# MCU.net
KiCad netlist of a schematic drawn in Altium Designer
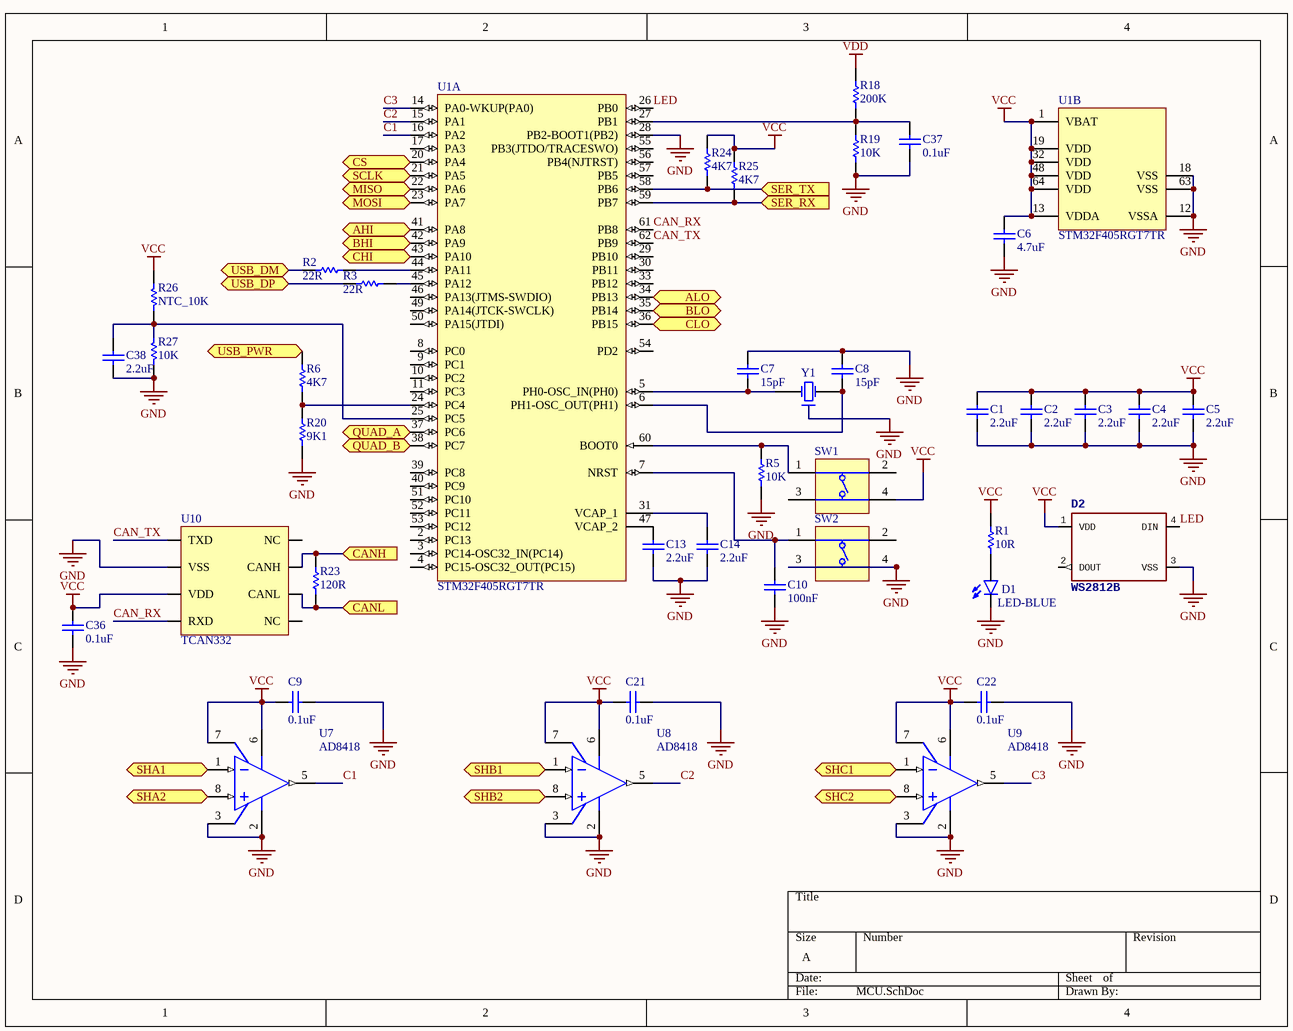
[diagram p0: MCU.SchDoc]

(export (version "E")
  (design (tool "Eeschema 10.0.6"))
  (components
    (comp (ref "C1")
      (value "2.2uF")
      (footprint "CAPC0402(1005)60_M")
      (description "CAP 2.2uF 6.3V ±10% 0402 (1005 Metric) Thickness 0.6mm SMD")
      (fields (field (name "TOLERANCE") "Â±10%"))
      (libsource (lib "Altium Content Vault") (part "CMP-1034-02125-1"))
    )
    (comp (ref "C2")
      (value "2.2uF")
      (footprint "CAPC0402(1005)60_M")
      (description "CAP 2.2uF 6.3V ±10% 0402 (1005 Metric) Thickness 0.6mm SMD")
      (fields (field (name "TOLERANCE") "Â±10%"))
      (libsource (lib "Altium Content Vault") (part "CMP-1034-02125-1"))
    )
    (comp (ref "C3")
      (value "2.2uF")
      (footprint "CAPC0402(1005)60_M")
      (description "CAP 2.2uF 6.3V ±10% 0402 (1005 Metric) Thickness 0.6mm SMD")
      (fields (field (name "TOLERANCE") "Â±10%"))
      (libsource (lib "Altium Content Vault") (part "CMP-1034-02125-1"))
    )
    (comp (ref "C4")
      (value "2.2uF")
      (footprint "CAPC0402(1005)60_M")
      (description "CAP 2.2uF 6.3V ±10% 0402 (1005 Metric) Thickness 0.6mm SMD")
      (fields (field (name "TOLERANCE") "Â±10%"))
      (libsource (lib "Altium Content Vault") (part "CMP-1034-02125-1"))
    )
    (comp (ref "C5")
      (value "2.2uF")
      (footprint "CAPC0402(1005)60_M")
      (description "CAP 2.2uF 6.3V ±10% 0402 (1005 Metric) Thickness 0.6mm SMD")
      (fields (field (name "TOLERANCE") "Â±10%"))
      (libsource (lib "Altium Content Vault") (part "CMP-1034-02125-1"))
    )
    (comp (ref "C6")
      (value "4.7uF")
      (footprint "CAPC0402(1005)60_L")
      (description "CAP 4.7uF 6.3V ±10% 0402 (1005 Metric) Thickness 0.6mm SMD")
      (fields (field (name "TOLERANCE") "Â±10%"))
      (libsource (lib "Altium Content Vault") (part "CMP-1034-02136-1"))
    )
    (comp (ref "C7")
      (value "15pF")
      (footprint "CAPC0402(1005)60_M")
      (description "CAP 15nF 6.3V ±10% 0402 (1005 Metric) Thickness 0.6mm SMD")
      (fields (field (name "TOLERANCE") "Â±10%"))
      (libsource (lib "Altium Content Vault") (part "CMP-1034-01906-1"))
    )
    (comp (ref "C8")
      (value "15pF")
      (footprint "CAPC0402(1005)60_M")
      (description "CAP 15nF 6.3V ±10% 0402 (1005 Metric) Thickness 0.6mm SMD")
      (fields (field (name "TOLERANCE") "Â±10%"))
      (libsource (lib "Altium Content Vault") (part "CMP-1034-01906-1"))
    )
    (comp (ref "C9")
      (value "0.1uF")
      (footprint "CAPC0402(1005)60_M")
      (description "CAP 100nF 6.3V ±5% 0402 (1005 Metric) Thickness 0.6mm SMD")
      (fields (field (name "TOLERANCE") "Â±5%"))
      (libsource (lib "Altium Content Vault") (part "CAP"))
    )
    (comp (ref "C10")
      (value "100nF")
      (footprint "CAPC0402(1005)60_M")
      (description "CAP 100nF 6.3V ±5% 0402 (1005 Metric) Thickness 0.6mm SMD")
      (fields (field (name "TOLERANCE") "Â±5%"))
      (libsource (lib "Altium Content Vault") (part "CAP"))
    )
    (comp (ref "C13")
      (value "2.2uF")
      (footprint "CAPC0402(1005)60_M")
      (description "CAP 2.2uF 6.3V ±10% 0402 (1005 Metric) Thickness 0.6mm SMD")
      (fields (field (name "TOLERANCE") "Â±10%"))
      (libsource (lib "Altium Content Vault") (part "CMP-1034-02125-1"))
    )
    (comp (ref "C14")
      (value "2.2uF")
      (footprint "CAPC0402(1005)60_M")
      (description "CAP 2.2uF 6.3V ±10% 0402 (1005 Metric) Thickness 0.6mm SMD")
      (fields (field (name "TOLERANCE") "Â±10%"))
      (libsource (lib "Altium Content Vault") (part "CMP-1034-02125-1"))
    )
    (comp (ref "C21")
      (value "0.1uF")
      (footprint "CAPC0402(1005)60_M")
      (description "CAP 100nF 6.3V ±5% 0402 (1005 Metric) Thickness 0.6mm SMD")
      (fields (field (name "TOLERANCE") "Â±5%"))
      (libsource (lib "Altium Content Vault") (part "CAP"))
    )
    (comp (ref "C22")
      (value "0.1uF")
      (footprint "CAPC0402(1005)60_M")
      (description "CAP 100nF 6.3V ±5% 0402 (1005 Metric) Thickness 0.6mm SMD")
      (fields (field (name "TOLERANCE") "Â±5%"))
      (libsource (lib "Altium Content Vault") (part "CAP"))
    )
    (comp (ref "C36")
      (value "0.1uF")
      (footprint "CAPC0402(1005)60_M")
      (description "CAP 100nF 6.3V ±5% 0402 (1005 Metric) Thickness 0.6mm SMD")
      (fields (field (name "TOLERANCE") "Â±5%"))
      (libsource (lib "Altium Content Vault") (part "CMP-1034-02060-1"))
    )
    (comp (ref "C37")
      (value "0.1uF")
      (footprint "CAPC0402(1005)60_L")
      (description "CAP 100nF 6.3V ±5% 0402 (1005 Metric) Thickness 0.6mm SMD")
      (fields (field (name "TOLERANCE") "Â±5%"))
      (libsource (lib "Altium Content Vault") (part "CMP-1034-02060-1"))
    )
    (comp (ref "C38")
      (value "2.2uF")
      (footprint "CAPC0402(1005)60_L")
      (description "CAP 2.2uF 6.3V ±10% 0402 (1005 Metric) Thickness 0.6mm SMD")
      (fields (field (name "TOLERANCE") "Â±10%"))
      (libsource (lib "Altium Content Vault") (part "CAP"))
    )
    (comp (ref "D1")
      (value "LED-BLUE")
      (footprint "LED-1206")
      (libsource (lib "Components") (part "LED-BLUE1206"))
    )
    (comp (ref "D2") (value "WS2812B") (footprint "WS2812B") (libsource (lib "Components") (part "WS2812B")))
    (comp (ref "R1")
      (value "10R")
      (footprint "RESC0402(1005)_N")
      (description "10R 0.063W 5% 0402 (1005 Metric)  SMD")
      (fields (field (name "POWER") "0.063 W") (field (name "TOLERANCE") "5 %"))
      (libsource (lib "Altium Content Vault") (part "CMP-1011-00026-1"))
    )
    (comp (ref "R2")
      (value "22R")
      (footprint "RESC0402(1005)_N")
      (description "22R 0.063W 5% 0402 (1005 Metric)  SMD")
      (fields (field (name "POWER") "0.063 W") (field (name "TOLERANCE") "5 %"))
      (libsource (lib "Altium Content Vault") (part "CMP-1011-00034-1"))
    )
    (comp (ref "R3")
      (value "22R")
      (footprint "RESC0402(1005)_N")
      (description "22R 0.063W 5% 0402 (1005 Metric)  SMD")
      (fields (field (name "POWER") "0.063 W") (field (name "TOLERANCE") "5 %"))
      (libsource (lib "Altium Content Vault") (part "CMP-1011-00034-1"))
    )
    (comp (ref "R5")
      (value "10K")
      (footprint "RESC0402(1005)_N")
      (description "10K 0.063W 5% 0402 (1005 Metric)  SMD")
      (fields (field (name "TOLERANCE") "5 %") (field (name "POWER") "0.063 W"))
      (libsource (lib "Altium Content Vault") (part "RES"))
    )
    (comp (ref "R6")
      (value "4K7")
      (footprint "RESC0402(1005)_L")
      (description "4K7 0.063W 5% 0402 (1005 Metric)  SMD")
      (fields (field (name "TOLERANCE") "5 %") (field (name "POWER") "0.063 W"))
      (libsource (lib "Altium Content Vault") (part "RES"))
    )
    (comp (ref "R18")
      (value "200K")
      (footprint "RESC0402(1005)_N")
      (description "5K1 0.063W 5% 0402 (1005 Metric)  SMD")
      (fields (field (name "TOLERANCE") "5 %") (field (name "POWER") "0.063 W"))
      (libsource (lib "Altium Content Vault") (part "CMP-1011-00091-1"))
    )
    (comp (ref "R19")
      (value "10K")
      (footprint "RESC0402(1005)_N")
      (description "10K 0.063W 5% 0402 (1005 Metric)  SMD")
      (fields (field (name "TOLERANCE") "5 %") (field (name "POWER") "0.063 W"))
      (libsource (lib "Altium Content Vault") (part "RES"))
    )
    (comp (ref "R20")
      (value "9K1")
      (footprint "RESC0402(1005)_M")
      (description "9K1 0.063W 5% 0402 (1005 Metric)  SMD")
      (fields (field (name "TOLERANCE") "5 %") (field (name "POWER") "0.063 W"))
      (libsource (lib "Altium Content Vault") (part "RES"))
    )
    (comp (ref "R23")
      (value "120R")
      (footprint "RESC0402(1005)_N")
      (description "120R 0.063W 5% 0402 (1005 Metric)  SMD")
      (fields (field (name "TOLERANCE") "5 %") (field (name "POWER") "0.063 W"))
      (libsource (lib "Altium Content Vault") (part "RES"))
    )
    (comp (ref "R24")
      (value "4K7")
      (footprint "RESC0402(1005)_L")
      (description "4K7 0.063W 5% 0402 (1005 Metric)  SMD")
      (fields (field (name "TOLERANCE") "5 %") (field (name "POWER") "0.063 W"))
      (libsource (lib "Altium Content Vault") (part "RES"))
    )
    (comp (ref "R25")
      (value "4K7")
      (footprint "RESC0402(1005)_L")
      (description "4K7 0.063W 5% 0402 (1005 Metric)  SMD")
      (fields (field (name "TOLERANCE") "5 %") (field (name "POWER") "0.063 W"))
      (libsource (lib "Altium Content Vault") (part "RES"))
    )
    (comp (ref "R26")
      (value "NTC_10K")
      (footprint "RESC0402(1005)_L")
      (description "10K 0.063W 1% 0402 (1005 Metric)  SMD")
      (fields (field (name "TOLERANCE") "1 %") (field (name "POWER") "0.063 W"))
      (libsource (lib "Altium Content Vault") (part "CMP-1011-00623-1"))
    )
    (comp (ref "R27")
      (value "10K")
      (footprint "RESC0402(1005)_L")
      (description "10K 0.063W 1% 0402 (1005 Metric)  SMD")
      (fields (field (name "TOLERANCE") "1 %") (field (name "POWER") "0.063 W"))
      (libsource (lib "Altium Content Vault") (part "CMP-1011-00623-1"))
    )
    (comp (ref "SW1")
      (value "~")
      (footprint "SWITCH")
      (description "Switch, SPNO Push Button SMD")
      (fields (field (name "MANUFACTURER") "Diptronics") (field (name "PARTNUMBER") "DTSM-61NT/R"))
      (libsource (lib "altium-import") (part "root_0_DIPT-DTSM-6_"))
    )
    (comp (ref "SW2")
      (value "~")
      (footprint "SWITCH")
      (description "Switch, SPNO Push Button SMD")
      (fields (field (name "MANUFACTURER") "Diptronics") (field (name "PARTNUMBER") "DTSM-61NT/R"))
      (libsource (lib "altium-import") (part "root_0_DIPT-DTSM-6_"))
    )
    (comp (ref "U1")
      (value "STM32F405RGT7TR")
      (footprint "STM-LQFP64_V")
      (fields (field (name "MANUFACTURER") "STMicroelectronics"))
      (libsource (lib "Altium Content Vault") (part "MC-ARM-STM32F4X5-SQ64"))
    )
    (comp (ref "U7") (value "AD8418") (footprint "MSOP-8") (libsource (lib "Components") (part "AD8418")))
    (comp (ref "U8") (value "AD8418") (footprint "MSOP-8") (libsource (lib "Components") (part "AD8418")))
    (comp (ref "U9") (value "AD8418") (footprint "MSOP-8") (libsource (lib "Components") (part "AD8418")))
    (comp (ref "U10") (value "TCAN332") (footprint "SOIC8") (libsource (lib "Components") (part "TCAN332")))
    (comp (ref "Y1")
      (value "~")
      (footprint "ABRA-ABM3B-4_V")
      (libsource (lib "Components") (part "ABRA-ABM3B-4"))
    )
  )
  (nets
    (net (code "1") (name "/AHI") (class "Default")
      (node (ref "U1") (pin "41") (pinfunction "PA8_41") (pintype "bidirectional"))
    )
    (net (code "2") (name "/ALO") (class "Default")
      (node (ref "U1") (pin "34") (pinfunction "PB13_34") (pintype "bidirectional"))
    )
    (net (code "3") (name "/BHI") (class "Default")
      (node (ref "U1") (pin "42") (pinfunction "PA9_42") (pintype "bidirectional"))
    )
    (net (code "4") (name "/BLO") (class "Default")
      (node (ref "U1") (pin "35") (pinfunction "PB14_35") (pintype "bidirectional"))
    )
    (net (code "5") (name "/C1") (class "Default")
      (node (ref "U1") (pin "16") (pinfunction "PA2_16") (pintype "bidirectional"))
      (node (ref "U7") (pin "5") (pinfunction "OUT_5") (pintype "output"))
    )
    (net (code "6") (name "/C2") (class "Default")
      (node (ref "U1") (pin "15") (pinfunction "PA1_15") (pintype "bidirectional"))
      (node (ref "U8") (pin "5") (pinfunction "OUT_5") (pintype "output"))
    )
    (net (code "7") (name "/C3") (class "Default")
      (node (ref "U1") (pin "14") (pinfunction "PA0-WKUP(PA0)_14") (pintype "bidirectional"))
      (node (ref "U9") (pin "5") (pinfunction "OUT_5") (pintype "output"))
    )
    (net (code "8") (name "/CANH") (class "Default")
      (node (ref "R23") (pin "2") (pinfunction "2_2") (pintype "passive"))
      (node (ref "U10") (pin "7") (pinfunction "CANH_7") (pintype "passive"))
    )
    (net (code "9") (name "/CANL") (class "Default")
      (node (ref "R23") (pin "1") (pinfunction "1_1") (pintype "passive"))
      (node (ref "U10") (pin "6") (pinfunction "CANL_6") (pintype "passive"))
    )
    (net (code "10") (name "/CAN_RX") (class "Default")
      (node (ref "U1") (pin "61") (pinfunction "PB8_61") (pintype "bidirectional"))
      (node (ref "U10") (pin "4") (pinfunction "RXD_4") (pintype "passive"))
    )
    (net (code "11") (name "/CAN_TX") (class "Default")
      (node (ref "U1") (pin "62") (pinfunction "PB9_62") (pintype "bidirectional"))
      (node (ref "U10") (pin "1") (pinfunction "TXD_1") (pintype "passive"))
    )
    (net (code "12") (name "/CHI") (class "Default")
      (node (ref "U1") (pin "43") (pinfunction "PA10_43") (pintype "bidirectional"))
    )
    (net (code "13") (name "/CLO") (class "Default")
      (node (ref "U1") (pin "36") (pinfunction "PB15_36") (pintype "bidirectional"))
    )
    (net (code "14") (name "/CS") (class "Default")
      (node (ref "U1") (pin "20") (pinfunction "PA4_20") (pintype "bidirectional"))
    )
    (net (code "15") (name "/LED") (class "Default")
      (node (ref "D2") (pin "4") (pinfunction "DIN_4") (pintype "passive"))
      (node (ref "U1") (pin "26") (pinfunction "PB0_26") (pintype "bidirectional"))
    )
    (net (code "16") (name "/MISO") (class "Default")
      (node (ref "U1") (pin "22") (pinfunction "PA6_22") (pintype "bidirectional"))
    )
    (net (code "17") (name "/MOSI") (class "Default")
      (node (ref "U1") (pin "23") (pinfunction "PA7_23") (pintype "bidirectional"))
    )
    (net (code "18") (name "/QUAD_A") (class "Default")
      (node (ref "U1") (pin "37") (pinfunction "PC6_37") (pintype "bidirectional"))
    )
    (net (code "19") (name "/QUAD_B") (class "Default")
      (node (ref "U1") (pin "38") (pinfunction "PC7_38") (pintype "bidirectional"))
    )
    (net (code "20") (name "/SCLK") (class "Default")
      (node (ref "U1") (pin "21") (pinfunction "PA5_21") (pintype "bidirectional"))
    )
    (net (code "21") (name "/SER_RX") (class "Default")
      (node (ref "R25") (pin "1") (pinfunction "1_1") (pintype "passive"))
      (node (ref "U1") (pin "59") (pinfunction "PB7_59") (pintype "bidirectional"))
    )
    (net (code "22") (name "/SER_TX") (class "Default")
      (node (ref "R24") (pin "1") (pinfunction "1_1") (pintype "passive"))
      (node (ref "U1") (pin "58") (pinfunction "PB6_58") (pintype "bidirectional"))
    )
    (net (code "23") (name "/SHA1") (class "Default")
      (node (ref "U7") (pin "1") (pinfunction "IN-_1") (pintype "input"))
    )
    (net (code "24") (name "/SHA2") (class "Default")
      (node (ref "U7") (pin "8") (pinfunction "IN+_8") (pintype "input"))
    )
    (net (code "25") (name "/SHB1") (class "Default")
      (node (ref "U8") (pin "1") (pinfunction "IN-_1") (pintype "input"))
    )
    (net (code "26") (name "/SHB2") (class "Default")
      (node (ref "U8") (pin "8") (pinfunction "IN+_8") (pintype "input"))
    )
    (net (code "27") (name "/SHC1") (class "Default")
      (node (ref "U9") (pin "1") (pinfunction "IN-_1") (pintype "input"))
    )
    (net (code "28") (name "/SHC2") (class "Default")
      (node (ref "U9") (pin "8") (pinfunction "IN+_8") (pintype "input"))
    )
    (net (code "29") (name "/USB_DM") (class "Default")
      (node (ref "R2") (pin "1") (pinfunction "1_1") (pintype "passive"))
    )
    (net (code "30") (name "/USB_DP") (class "Default")
      (node (ref "R3") (pin "1") (pinfunction "1_1") (pintype "passive"))
    )
    (net (code "31") (name "/USB_PWR") (class "Default")
      (node (ref "R6") (pin "2") (pinfunction "2_2") (pintype "passive"))
    )
    (net (code "32") (name "GND") (class "Default")
      (node (ref "C1") (pin "1") (pinfunction "1_1") (pintype "passive"))
      (node (ref "C10") (pin "1") (pinfunction "1_1") (pintype "passive"))
      (node (ref "C13") (pin "1") (pinfunction "1_1") (pintype "passive"))
      (node (ref "C14") (pin "1") (pinfunction "1_1") (pintype "passive"))
      (node (ref "C2") (pin "1") (pinfunction "1_1") (pintype "passive"))
      (node (ref "C21") (pin "2") (pinfunction "2_2") (pintype "passive"))
      (node (ref "C22") (pin "2") (pinfunction "2_2") (pintype "passive"))
      (node (ref "C3") (pin "1") (pinfunction "1_1") (pintype "passive"))
      (node (ref "C36") (pin "1") (pinfunction "1_1") (pintype "passive"))
      (node (ref "C37") (pin "1") (pinfunction "1_1") (pintype "passive"))
      (node (ref "C38") (pin "1") (pinfunction "1_1") (pintype "passive"))
      (node (ref "C4") (pin "1") (pinfunction "1_1") (pintype "passive"))
      (node (ref "C5") (pin "1") (pinfunction "1_1") (pintype "passive"))
      (node (ref "C6") (pin "1") (pinfunction "1_1") (pintype "passive"))
      (node (ref "C7") (pin "2") (pinfunction "2_2") (pintype "passive"))
      (node (ref "C8") (pin "2") (pinfunction "2_2") (pintype "passive"))
      (node (ref "C9") (pin "2") (pinfunction "2_2") (pintype "passive"))
      (node (ref "D1") (pin "C") (pinfunction "C_C") (pintype "passive"))
      (node (ref "D2") (pin "3") (pinfunction "VSS_3") (pintype "power_in"))
      (node (ref "R19") (pin "1") (pinfunction "1_1") (pintype "passive"))
      (node (ref "R20") (pin "1") (pinfunction "1_1") (pintype "passive"))
      (node (ref "R27") (pin "1") (pinfunction "1_1") (pintype "passive"))
      (node (ref "R5") (pin "1") (pinfunction "1_1") (pintype "passive"))
      (node (ref "SW2") (pin "3") (pinfunction "T3_3") (pintype "passive"))
      (node (ref "SW2") (pin "4") (pinfunction "T3_4") (pintype "passive"))
      (node (ref "U1") (pin "12") (pinfunction "VSSA_12") (pintype "power_in"))
      (node (ref "U1") (pin "18") (pinfunction "VSS_18") (pintype "power_in"))
      (node (ref "U1") (pin "28") (pinfunction "PB2-BOOT1(PB2)_28") (pintype "bidirectional"))
      (node (ref "U1") (pin "63") (pinfunction "VSS_63") (pintype "power_in"))
      (node (ref "U10") (pin "2") (pinfunction "VSS_2") (pintype "passive"))
      (node (ref "U7") (pin "2") (pinfunction "GND_2") (pintype "power_in"))
      (node (ref "U7") (pin "3") (pinfunction "VREF2_3") (pintype "passive"))
      (node (ref "U8") (pin "2") (pinfunction "GND_2") (pintype "power_in"))
      (node (ref "U8") (pin "3") (pinfunction "VREF2_3") (pintype "passive"))
      (node (ref "U9") (pin "2") (pinfunction "GND_2") (pintype "power_in"))
      (node (ref "U9") (pin "3") (pinfunction "VREF2_3") (pintype "passive"))
      (node (ref "Y1") (pin "2") (pinfunction "2_2") (pintype "passive"))
    )
    (net (code "33") (name "Net-(D1-PadA)") (class "Default")
      (node (ref "D1") (pin "A") (pinfunction "A_A") (pintype "passive"))
      (node (ref "R1") (pin "1") (pinfunction "1_1") (pintype "passive"))
    )
    (net (code "34") (name "Net-(SW1-T1)") (class "Default")
      (node (ref "R5") (pin "2") (pinfunction "2_2") (pintype "passive"))
      (node (ref "SW1") (pin "1") (pinfunction "T1_1") (pintype "passive"))
      (node (ref "U1") (pin "60") (pinfunction "BOOT0_60") (pintype "input"))
    )
    (net (code "35") (name "Net-(SW2-T1)") (class "Default")
      (node (ref "C10") (pin "2") (pinfunction "2_2") (pintype "passive"))
      (node (ref "SW2") (pin "1") (pinfunction "T1_1") (pintype "passive"))
      (node (ref "U1") (pin "7") (pinfunction "NRST_7") (pintype "bidirectional"))
    )
    (net (code "36") (name "Net-(U1A-PA11)") (class "Default")
      (node (ref "R2") (pin "2") (pinfunction "2_2") (pintype "passive"))
      (node (ref "U1") (pin "44") (pinfunction "PA11_44") (pintype "bidirectional"))
    )
    (net (code "37") (name "Net-(U1A-PA12)") (class "Default")
      (node (ref "R3") (pin "2") (pinfunction "2_2") (pintype "passive"))
      (node (ref "U1") (pin "45") (pinfunction "PA12_45") (pintype "bidirectional"))
    )
    (net (code "38") (name "Net-(U1A-PB1)") (class "Default")
      (node (ref "C37") (pin "2") (pinfunction "2_2") (pintype "passive"))
      (node (ref "R18") (pin "2") (pinfunction "2_2") (pintype "passive"))
      (node (ref "R19") (pin "2") (pinfunction "2_2") (pintype "passive"))
      (node (ref "U1") (pin "27") (pinfunction "PB1_27") (pintype "bidirectional"))
    )
    (net (code "39") (name "Net-(U1A-PC4)") (class "Default")
      (node (ref "R20") (pin "2") (pinfunction "2_2") (pintype "passive"))
      (node (ref "R6") (pin "1") (pinfunction "1_1") (pintype "passive"))
      (node (ref "U1") (pin "24") (pinfunction "PC4_24") (pintype "bidirectional"))
    )
    (net (code "40") (name "Net-(U1A-PC5)") (class "Default")
      (node (ref "C38") (pin "2") (pinfunction "2_2") (pintype "passive"))
      (node (ref "R26") (pin "1") (pinfunction "1_1") (pintype "passive"))
      (node (ref "R27") (pin "2") (pinfunction "2_2") (pintype "passive"))
      (node (ref "U1") (pin "25") (pinfunction "PC5_25") (pintype "bidirectional"))
    )
    (net (code "41") (name "Net-(U1A-PH0-OSC_IN(PH0))") (class "Default")
      (node (ref "C7") (pin "1") (pinfunction "1_1") (pintype "passive"))
      (node (ref "U1") (pin "5") (pinfunction "PH0-OSC_IN(PH0)_5") (pintype "bidirectional"))
      (node (ref "Y1") (pin "1") (pinfunction "X1_1") (pintype "passive"))
    )
    (net (code "42") (name "Net-(U1A-PH1-OSC_OUT(PH1))") (class "Default")
      (node (ref "C8") (pin "1") (pinfunction "1_1") (pintype "passive"))
      (node (ref "U1") (pin "6") (pinfunction "PH1-OSC_OUT(PH1)_6") (pintype "bidirectional"))
      (node (ref "Y1") (pin "3") (pinfunction "X2_3") (pintype "passive"))
    )
    (net (code "43") (name "Net-(U1A-VCAP_1)") (class "Default")
      (node (ref "C14") (pin "2") (pinfunction "2_2") (pintype "passive"))
      (node (ref "U1") (pin "31") (pinfunction "VCAP_1_31") (pintype "power_in"))
    )
    (net (code "44") (name "Net-(U1A-VCAP_2)") (class "Default")
      (node (ref "C13") (pin "2") (pinfunction "2_2") (pintype "passive"))
      (node (ref "U1") (pin "47") (pinfunction "VCAP_2_47") (pintype "power_in"))
    )
    (net (code "45") (name "VCC") (class "Default")
      (node (ref "C1") (pin "2") (pinfunction "2_2") (pintype "passive"))
      (node (ref "C2") (pin "2") (pinfunction "2_2") (pintype "passive"))
      (node (ref "C21") (pin "1") (pinfunction "1_1") (pintype "passive"))
      (node (ref "C22") (pin "1") (pinfunction "1_1") (pintype "passive"))
      (node (ref "C3") (pin "2") (pinfunction "2_2") (pintype "passive"))
      (node (ref "C36") (pin "2") (pinfunction "2_2") (pintype "passive"))
      (node (ref "C4") (pin "2") (pinfunction "2_2") (pintype "passive"))
      (node (ref "C5") (pin "2") (pinfunction "2_2") (pintype "passive"))
      (node (ref "C6") (pin "2") (pinfunction "2_2") (pintype "passive"))
      (node (ref "C9") (pin "1") (pinfunction "1_1") (pintype "passive"))
      (node (ref "D2") (pin "1") (pinfunction "VDD_1") (pintype "power_in"))
      (node (ref "R1") (pin "2") (pinfunction "2_2") (pintype "passive"))
      (node (ref "R24") (pin "2") (pinfunction "2_2") (pintype "passive"))
      (node (ref "R25") (pin "2") (pinfunction "2_2") (pintype "passive"))
      (node (ref "R26") (pin "2") (pinfunction "2_2") (pintype "passive"))
      (node (ref "SW1") (pin "4") (pinfunction "T3_4") (pintype "passive"))
      (node (ref "U1") (pin "1") (pinfunction "VBAT_1") (pintype "power_in"))
      (node (ref "U1") (pin "13") (pinfunction "VDDA_13") (pintype "power_in"))
      (node (ref "U1") (pin "19") (pinfunction "VDD_19") (pintype "power_in"))
      (node (ref "U1") (pin "32") (pinfunction "VDD_32") (pintype "power_in"))
      (node (ref "U1") (pin "48") (pinfunction "VDD_48") (pintype "power_in"))
      (node (ref "U1") (pin "64") (pinfunction "VDD_64") (pintype "power_in"))
      (node (ref "U10") (pin "3") (pinfunction "VDD_3") (pintype "passive"))
      (node (ref "U7") (pin "6") (pinfunction "VS_6") (pintype "power_in"))
      (node (ref "U7") (pin "7") (pinfunction "VREF1_7") (pintype "passive"))
      (node (ref "U8") (pin "6") (pinfunction "VS_6") (pintype "power_in"))
      (node (ref "U8") (pin "7") (pinfunction "VREF1_7") (pintype "passive"))
      (node (ref "U9") (pin "6") (pinfunction "VS_6") (pintype "power_in"))
      (node (ref "U9") (pin "7") (pinfunction "VREF1_7") (pintype "passive"))
    )
    (net (code "46") (name "VDD") (class "Default")
      (node (ref "R18") (pin "1") (pinfunction "1_1") (pintype "passive"))
    )
    (net (code "47") (name "unconnected-(D2-DOUT-Pad2)") (class "Default")
      (node (ref "D2") (pin "2") (pinfunction "DOUT_2") (pintype "output"))
    )
    (net (code "48") (name "unconnected-(SW1-T2-Pad2)") (class "Default")
      (node (ref "SW1") (pin "2") (pinfunction "T2_2") (pintype "passive"))
    )
    (net (code "49") (name "unconnected-(SW1-T3-Pad3)") (class "Default")
      (node (ref "SW1") (pin "3") (pinfunction "T3_3") (pintype "passive"))
    )
    (net (code "50") (name "unconnected-(SW2-T2-Pad2)") (class "Default")
      (node (ref "SW2") (pin "2") (pinfunction "T2_2") (pintype "passive"))
    )
    (net (code "51") (name "unconnected-(U1A-PA3-Pad17)") (class "Default")
      (node (ref "U1") (pin "17") (pinfunction "PA3_17") (pintype "bidirectional"))
    )
    (net (code "52") (name "unconnected-(U1A-PA13(JTMS-SWDIO)-Pad46)") (class "Default")
      (node (ref "U1") (pin "46") (pinfunction "PA13(JTMS-SWDIO)_46") (pintype "bidirectional"))
    )
    (net (code "53") (name "unconnected-(U1A-PA14(JTCK-SWCLK)-Pad49)") (class "Default")
      (node (ref "U1") (pin "49") (pinfunction "PA14(JTCK-SWCLK)_49") (pintype "bidirectional"))
    )
    (net (code "54") (name "unconnected-(U1A-PA15(JTDI)-Pad50)") (class "Default")
      (node (ref "U1") (pin "50") (pinfunction "PA15(JTDI)_50") (pintype "bidirectional"))
    )
    (net (code "55") (name "unconnected-(U1A-PB3(JTDO{slash}TRACESWO)-Pad55)") (class "Default")
      (node (ref "U1") (pin "55") (pinfunction "PB3(JTDO/TRACESWO)_55") (pintype "bidirectional"))
    )
    (net (code "56") (name "unconnected-(U1A-PB4(NJTRST)-Pad56)") (class "Default")
      (node (ref "U1") (pin "56") (pinfunction "PB4(NJTRST)_56") (pintype "bidirectional"))
    )
    (net (code "57") (name "unconnected-(U1A-PB5-Pad57)") (class "Default")
      (node (ref "U1") (pin "57") (pinfunction "PB5_57") (pintype "bidirectional"))
    )
    (net (code "58") (name "unconnected-(U1A-PB10-Pad29)") (class "Default")
      (node (ref "U1") (pin "29") (pinfunction "PB10_29") (pintype "bidirectional"))
    )
    (net (code "59") (name "unconnected-(U1A-PB11-Pad30)") (class "Default")
      (node (ref "U1") (pin "30") (pinfunction "PB11_30") (pintype "bidirectional"))
    )
    (net (code "60") (name "unconnected-(U1A-PB12-Pad33)") (class "Default")
      (node (ref "U1") (pin "33") (pinfunction "PB12_33") (pintype "bidirectional"))
    )
    (net (code "61") (name "unconnected-(U1A-PC0-Pad8)") (class "Default")
      (node (ref "U1") (pin "8") (pinfunction "PC0_8") (pintype "bidirectional"))
    )
    (net (code "62") (name "unconnected-(U1A-PC1-Pad9)") (class "Default")
      (node (ref "U1") (pin "9") (pinfunction "PC1_9") (pintype "bidirectional"))
    )
    (net (code "63") (name "unconnected-(U1A-PC2-Pad10)") (class "Default")
      (node (ref "U1") (pin "10") (pinfunction "PC2_10") (pintype "bidirectional"))
    )
    (net (code "64") (name "unconnected-(U1A-PC3-Pad11)") (class "Default")
      (node (ref "U1") (pin "11") (pinfunction "PC3_11") (pintype "bidirectional"))
    )
    (net (code "65") (name "unconnected-(U1A-PC8-Pad39)") (class "Default")
      (node (ref "U1") (pin "39") (pinfunction "PC8_39") (pintype "bidirectional"))
    )
    (net (code "66") (name "unconnected-(U1A-PC9-Pad40)") (class "Default")
      (node (ref "U1") (pin "40") (pinfunction "PC9_40") (pintype "bidirectional"))
    )
    (net (code "67") (name "unconnected-(U1A-PC10-Pad51)") (class "Default")
      (node (ref "U1") (pin "51") (pinfunction "PC10_51") (pintype "bidirectional"))
    )
    (net (code "68") (name "unconnected-(U1A-PC11-Pad52)") (class "Default")
      (node (ref "U1") (pin "52") (pinfunction "PC11_52") (pintype "bidirectional"))
    )
    (net (code "69") (name "unconnected-(U1A-PC12-Pad53)") (class "Default")
      (node (ref "U1") (pin "53") (pinfunction "PC12_53") (pintype "bidirectional"))
    )
    (net (code "70") (name "unconnected-(U1A-PC13-Pad2)") (class "Default")
      (node (ref "U1") (pin "2") (pinfunction "PC13_2") (pintype "bidirectional"))
    )
    (net (code "71") (name "unconnected-(U1A-PC14-OSC32_IN(PC14)-Pad3)") (class "Default")
      (node (ref "U1") (pin "3") (pinfunction "PC14-OSC32_IN(PC14)_3") (pintype "bidirectional"))
    )
    (net (code "72") (name "unconnected-(U1A-PC15-OSC32_OUT(PC15)-Pad4)") (class "Default")
      (node (ref "U1") (pin "4") (pinfunction "PC15-OSC32_OUT(PC15)_4") (pintype "bidirectional"))
    )
    (net (code "73") (name "unconnected-(U1A-PD2-Pad54)") (class "Default")
      (node (ref "U1") (pin "54") (pinfunction "PD2_54") (pintype "bidirectional"))
    )
    (net (code "74") (name "unconnected-(U10-NC-Pad5)") (class "Default")
      (node (ref "U10") (pin "5") (pinfunction "NC_5") (pintype "passive"))
    )
    (net (code "75") (name "unconnected-(U10-NC-Pad8)") (class "Default")
      (node (ref "U10") (pin "8") (pinfunction "NC_8") (pintype "passive"))
    )
  )
)
